# power_section.net
KiCad netlist of a schematic drawn in Altium Designer
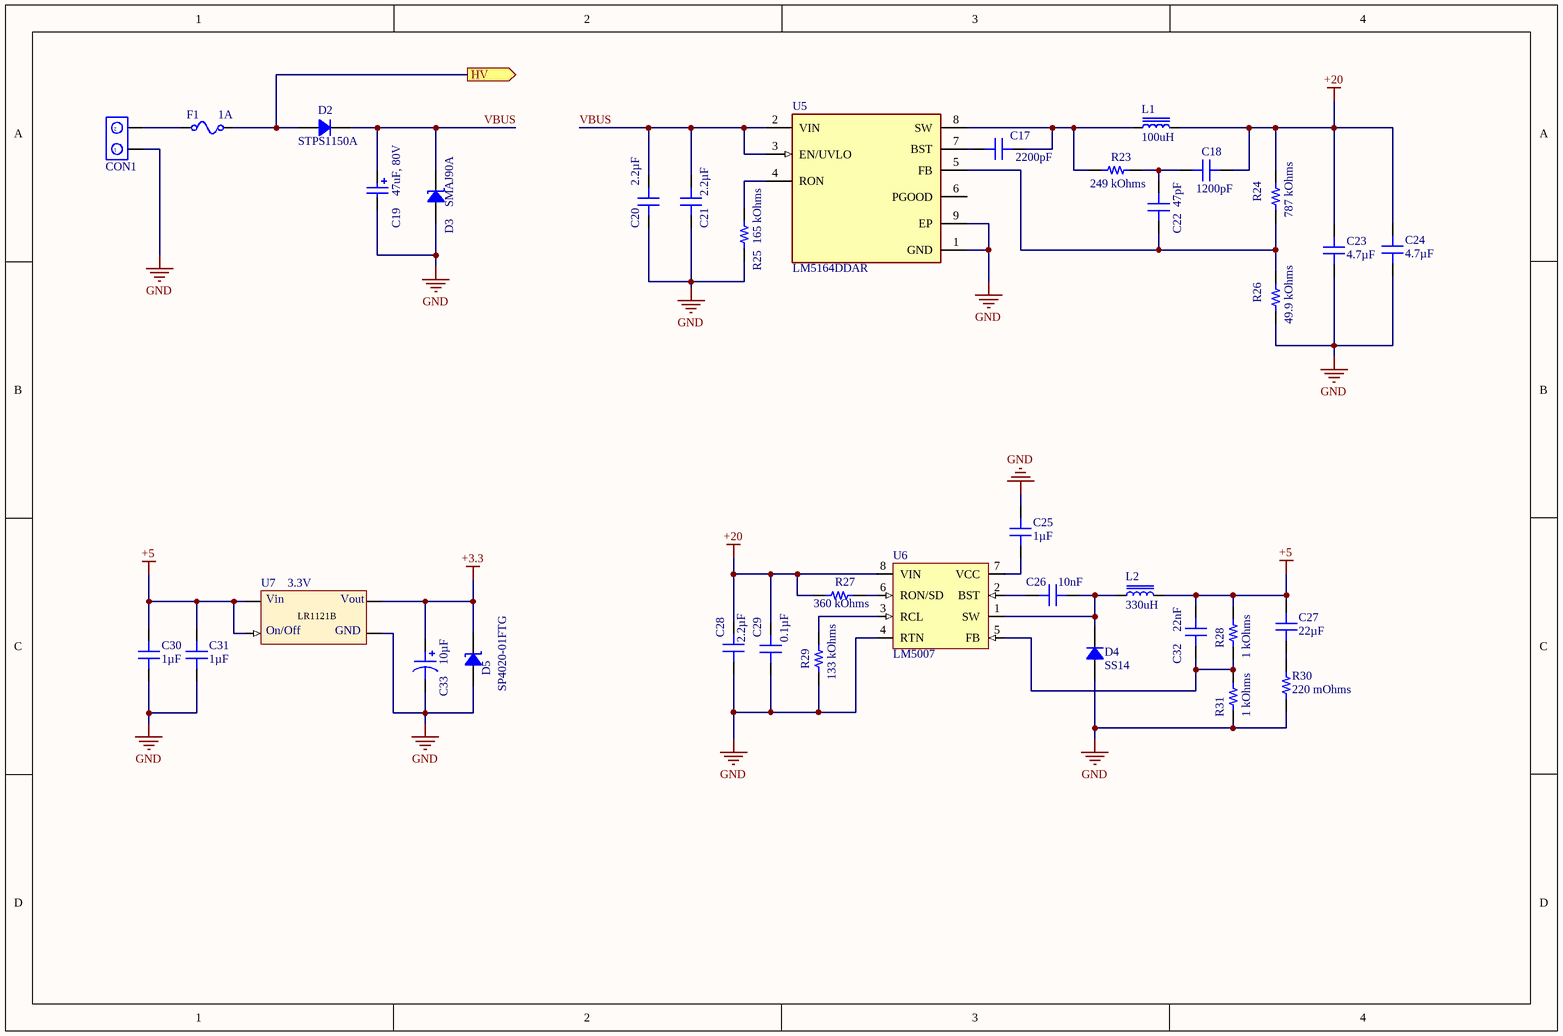
[diagram p0: power section.SchDoc]

(export (version "E")
  (design (tool "Eeschema 10.0.6"))
  (components
    (comp (ref "C17")
      (value "2200pF")
      (footprint "CAP 1206_3216 - 1.2MM")
      (description "CAP CER 1206 2.2NF 100V C0G")
      (fields (field (name "PART NUMBER") "C1206C222K1GECAUTO") (field (name "MANUFACTURER") "KEMET"))
      (libsource (lib "Celestial Altium Library - altium_library") (part "Capacitor"))
    )
    (comp (ref "C18")
      (value "1200pF")
      (footprint "CAP 0603_1608")
      (description "CAP CER 1200PF 100V X7R 0603")
      (fields (field (name "PART NUMBER") "C0603C122K1RAC7867") (field (name "MANUFACTURER") "KEMET"))
      (libsource (lib "Celestial Altium Library - altium_library") (part "Capacitor"))
    )
    (comp (ref "C19")
      (value "47uF, 80V")
      (footprint "WCAP-ASLI_D10H10.5")
      (description "WCAP-ASLI Aluminum Electrolytic Capacitor, V-Chip, SMT, D10xH10.5mm, 47uF, 80V")
      (fields
        (field (name "MANUFACTURER PART NUMBER") "865081757008")
        (field (name "MANUFACTURER") "Wurth Elektronik")
      )
      (libsource (lib "Altium_WCAP-ASLI_rev20b") (part "865081757008"))
    )
    (comp (ref "C20")
      (value "2.2µF")
      (footprint "CAP 1210_3225 - 2.8MM")
      (description "CAP CER 2.2UF 100V X7R 1210")
      (fields (field (name "PART NUMBER") "HMK325B7225KM-P") (field (name "MANUFACTURER") "Taiyo Yuden"))
      (libsource (lib "Celestial Altium Library - altium_library") (part "Capacitor"))
    )
    (comp (ref "C21")
      (value "2.2µF")
      (footprint "CAP 1210_3225 - 2.8MM")
      (description "CAP CER 2.2UF 100V X7R 1210")
      (fields (field (name "PART NUMBER") "HMK325B7225KM-P") (field (name "MANUFACTURER") "Taiyo Yuden"))
      (libsource (lib "Celestial Altium Library - altium_library") (part "Capacitor"))
    )
    (comp (ref "C22")
      (value "47pF")
      (footprint "CAP 0603_1608")
      (description "CAP CER 47PF 100V C0G/NP0 0603")
      (fields (field (name "PART NUMBER") "06031A470FAT2A") (field (name "MANUFACTURER") "AVX Corporation"))
      (libsource (lib "Celestial Altium Library - altium_library") (part "Capacitor"))
    )
    (comp (ref "C23")
      (value "4.7µF")
      (footprint "CAP 0805_2012")
      (description "CAP CER 4.7UF 50V X5R 0805")
      (fields
        (field (name "PART NUMBER") "CL21A475KBQNNNE")
        (field (name "MANUFACTURER") "Samsung Electro-Mechanics")
      )
      (libsource (lib "Celestial Altium Library - altium_library") (part "Capacitor"))
    )
    (comp (ref "C24")
      (value "4.7µF")
      (footprint "CAP 0805_2012")
      (description "CAP CER 4.7UF 50V X5R 0805")
      (fields
        (field (name "PART NUMBER") "CL21A475KBQNNNE")
        (field (name "MANUFACTURER") "Samsung Electro-Mechanics")
      )
      (libsource (lib "Celestial Altium Library - altium_library") (part "Capacitor"))
    )
    (comp (ref "C25")
      (value "1µF")
      (footprint "CAP 0805_2012")
      (description "CAP CER 1UF 50V X7R 0805")
      (fields
        (field (name "PART NUMBER") "GCM21BR71H105KA03L")
        (field (name "MANUFACTURER") "Murata Electronics")
      )
      (libsource (lib "Celestial Altium Library - altium_library") (part "Capacitor"))
    )
    (comp (ref "C26")
      (value "10nF")
      (footprint "CAP 0402_1005")
      (description "CAP CER 0402 10NF 16V X7R 10%")
      (fields (field (name "PART NUMBER") "C0402C103K4RECAUTO") (field (name "MANUFACTURER") "KEMET"))
      (libsource (lib "Celestial Altium Library - altium_library") (part "Capacitor"))
    )
    (comp (ref "C27")
      (value "22µF")
      (footprint "CAP 1210_3225 - 2.8MM")
      (description "CAP CER 22UF 25V X7R 1210")
      (fields
        (field (name "PART NUMBER") "C3225X7R1E226M250AB")
        (field (name "MANUFACTURER") "TDK Corporation")
      )
      (libsource (lib "Celestial Altium Library - altium_library") (part "Capacitor"))
    )
    (comp (ref "C28")
      (value "2.2µF")
      (footprint "CAP 1206_3216 - 1.0MM")
      (description "CAP CER 2.2UF 50V X7R 1206")
      (fields (field (name "PART NUMBER") "UMK316B7225MD-T") (field (name "MANUFACTURER") "Taiyo Yuden"))
      (libsource (lib "Celestial Altium Library - altium_library") (part "Capacitor"))
    )
    (comp (ref "C29")
      (value "0.1µF")
      (footprint "CAP 0805_2012")
      (description "CAP CER 0805 10% X8R 50V 100NF")
      (fields (field (name "PART NUMBER") "AC0805KKX8R9BB104") (field (name "MANUFACTURER") "Yageo"))
      (libsource (lib "Celestial Altium Library - altium_library") (part "Capacitor"))
    )
    (comp (ref "C30")
      (value "1µF")
      (footprint "CAP 0402_1005")
      (description "CAP CER 1UF 10V X7S 0402")
      (fields
        (field (name "PART NUMBER") "GRM155C71A105KE11D")
        (field (name "MANUFACTURER") "Murata Electronics")
      )
      (libsource (lib "Celestial Altium Library - altium_library") (part "Capacitor"))
    )
    (comp (ref "C31")
      (value "1µF")
      (footprint "CAP 0402_1005")
      (description "CAP CER 1UF 10V X7S 0402")
      (fields
        (field (name "PART NUMBER") "GRM155C71A105KE11D")
        (field (name "MANUFACTURER") "Murata Electronics")
      )
      (libsource (lib "Celestial Altium Library - altium_library") (part "Capacitor"))
    )
    (comp (ref "C32")
      (value "22nF")
      (footprint "CAP 0603_1608")
      (description "CAP CER 2200PF 50V X7R 0603")
      (fields (field (name "PART NUMBER") "06035C222JAT2A") (field (name "MANUFACTURER") "AVX Corporation"))
      (libsource (lib "Celestial Altium Library - altium_library") (part "Capacitor"))
    )
    (comp (ref "C33")
      (value "10µF")
      (footprint "CAP POL 1206_3216")
      (description "CAP TANT 10UF 10% 10V 1206")
      (fields (field (name "PART NUMBER") "T491S106K010AT") (field (name "MANUFACTURER") "KEMET"))
      (libsource (lib "Celestial Altium Library - altium_library") (part "Polarised Capacitor"))
    )
    (comp (ref "CON1")
      (value "DG301-5.0-02P-12-00AH")
      (footprint "DG301-5.0-02P-12-00AH")
      (libsource (lib "My_Library_PCB_Terminal") (part "DG301-5.0-02P-12-00AH"))
    )
    (comp (ref "D2")
      (value "STPS1150A")
      (footprint "DO214AC SMA")
      (description "DIODE SCHOTTKY 150V 1A SMA")
      (fields (field (name "MANUFACTURER") "STMicroelectronics"))
      (libsource (lib "Celestial Altium Library - altium_library") (part "Diode"))
    )
    (comp (ref "D3")
      (value "SMAJ90A")
      (footprint "DO214AC SMA")
      (description "TVS DIODE 90V 146V SMA")
      (fields (field (name "MANUFACTURER") "AVX Corporation"))
      (libsource (lib "Celestial Altium Library - altium_library") (part "DIODE TVS UNI"))
    )
    (comp (ref "D4")
      (value "SS14")
      (footprint "DO214AC SMA")
      (description "DIODE SCHOTTKY 40V 1A SMA")
      (fields (field (name "MANUFACTURER") "ON Semiconductor"))
      (libsource (lib "Celestial Altium Library - altium_library") (part "Diode"))
    )
    (comp (ref "D5")
      (value "SP4020-01FTG")
      (footprint "SOD323")
      (description "TVS DIODE 3.3V 21.8V SOD323")
      (fields (field (name "MANUFACTURER") "Littelfuse Inc."))
      (libsource (lib "Celestial Altium Library - altium_library") (part "DIODE TVS UNI"))
    )
    (comp (ref "F1")
      (value "1A")
      (footprint "5x20 fuse holder clip R3-5A")
      (description "5x20 fuse holder clip")
      (libsource (lib "My_Library_Fuse") (part "5x20 fuse"))
    )
    (comp (ref "L1")
      (value "100uH")
      (footprint "WE-PD_1245")
      (description "330uh 1A Shielded Fixed inductor COREMASTER")
      (fields (field (name "TOLERANCE") "20%"))
      (libsource (lib "My_Library_Fixed_Inductor") (part "CDRH127-101M"))
    )
    (comp (ref "L2")
      (value "330uH")
      (footprint "WE-PD_1245")
      (description "330uh 1A Shielded Fixed inductor COREMASTER")
      (fields (field (name "TOLERANCE") "20%"))
      (libsource (lib "My_Library_Fixed_Inductor") (part "SRI1204-331M"))
    )
    (comp (ref "R23")
      (value "249 kOhms")
      (footprint "RES 1206_3216")
      (description "RES SMD 249K OHM 1% 1/4W 1206")
      (fields (field (name "PART NUMBER") "CRCW1206249KFKEA") (field (name "MANUFACTURER") "Vishay Dale"))
      (libsource (lib "Celestial Altium Library - altium_library") (part "Resistor"))
    )
    (comp (ref "R24")
      (value "787 kOhms")
      (footprint "RES 1206_3216")
      (description "RES 787K OHM 1% 1/4W 1206")
      (fields
        (field (name "PART NUMBER") "RMCF1206FT787K")
        (field (name "MANUFACTURER") "Stackpole Electronics Inc")
      )
      (libsource (lib "Celestial Altium Library - altium_library") (part "Resistor"))
    )
    (comp (ref "R25")
      (value "165 kOhms")
      (footprint "RES 1206_3216")
      (description "RES SMD 165K OHM 1% 1/4W 1206")
      (fields (field (name "PART NUMBER") "CRCW1206165KFKEA") (field (name "MANUFACTURER") "Vishay Dale"))
      (libsource (lib "Celestial Altium Library - altium_library") (part "Resistor"))
    )
    (comp (ref "R26")
      (value "49.9 kOhms")
      (footprint "RES 1206_3216")
      (description "RES SMD 49.9K OHM 1% 1/4W 1206")
      (fields (field (name "PART NUMBER") "AC1206FR-0749K9L") (field (name "MANUFACTURER") "Yageo"))
      (libsource (lib "Celestial Altium Library - altium_library") (part "Resistor"))
    )
    (comp (ref "R27")
      (value "360 kOhms")
      (footprint "RES 1206_3216")
      (description "RES SMD 360K OHM 1% 1/4W 1206")
      (fields (field (name "PART NUMBER") "RC1206FR-07360KL") (field (name "MANUFACTURER") "Yageo"))
      (libsource (lib "Celestial Altium Library - altium_library") (part "Resistor"))
    )
    (comp (ref "R28")
      (value "1 kOhms")
      (footprint "RES 1206_3216")
      (description "RES SMD 1K OHM 1% 1/4W 1206")
      (fields (field (name "PART NUMBER") "RC1206FR-071KL") (field (name "MANUFACTURER") "Yageo"))
      (libsource (lib "Celestial Altium Library - altium_library") (part "Resistor"))
    )
    (comp (ref "R29")
      (value "133 kOhms")
      (footprint "RES 1206_3216")
      (description "RES SMD 133K OHM 1% 1/4W 1206")
      (fields (field (name "PART NUMBER") "RC1206FR-07133KL") (field (name "MANUFACTURER") "Yageo"))
      (libsource (lib "Celestial Altium Library - altium_library") (part "Resistor"))
    )
    (comp (ref "R30")
      (value "220 mOhms")
      (footprint "RES 1206_3216")
      (description "RES 0.22 OHM 1% 1/4W 1206")
      (fields
        (field (name "PART NUMBER") "RMCF1206FTR220")
        (field (name "MANUFACTURER") "Stackpole Electronics Inc")
      )
      (libsource (lib "Celestial Altium Library - altium_library") (part "Resistor"))
    )
    (comp (ref "R31")
      (value "1 kOhms")
      (footprint "RES 1206_3216")
      (description "RES SMD 1K OHM 1% 1/4W 1206")
      (fields (field (name "PART NUMBER") "RC1206FR-071KL") (field (name "MANUFACTURER") "Yageo"))
      (libsource (lib "Celestial Altium Library - altium_library") (part "Resistor"))
    )
    (comp (ref "U5")
      (value "LM5164DDAR")
      (footprint "FP-DDA0008E-IPC_A")
      (description "POWER MANAGEMENT")
      (fields
        (field (name "MANUFACTURER") "Texas Instruments")
        (field (name "OCTOPART") "https://octopart.com/lm5164ddar-texas+instruments-96785744")
      )
      (libsource (lib "My_Library_DCDC_Switching_Regulators") (part "LM5164DDAR"))
    )
    (comp (ref "U6")
      (value "LM5007")
      (footprint "DGK0008A_L")
      (description "High Voltage (80V) Step Down Switching Regulator, 8-pin MSOP")
      (fields (field (name "MANUFACTURER") "Texas Instruments"))
      (libsource (lib "My_Library_Switching_Regulators") (part "LM5007MM"))
    )
    (comp (ref "U7")
      (value "3.3V")
      (footprint "SOT25_LR2111")
      (description "200mA 7V LDO")
      (libsource (lib "My_Library_Linear_Regulator") (part "LR1121B_3V3"))
    )
  )
  (nets
    (net (code "1") (name "+3.3") (class "Default")
      (node (ref "C33") (pin "1") (pinfunction "1_1") (pintype "passive"))
      (node (ref "D5") (pin "2") (pinfunction "2_2") (pintype "passive"))
      (node (ref "U7") (pin "1") (pinfunction "Vout_1") (pintype "power_in"))
    )
    (net (code "2") (name "+5") (class "Default")
      (node (ref "C27") (pin "2") (pinfunction "2_2") (pintype "passive"))
      (node (ref "C30") (pin "2") (pinfunction "2_2") (pintype "passive"))
      (node (ref "C31") (pin "2") (pinfunction "2_2") (pintype "passive"))
      (node (ref "C32") (pin "2") (pinfunction "2_2") (pintype "passive"))
      (node (ref "L2") (pin "2") (pinfunction "2_2") (pintype "passive"))
      (node (ref "R28") (pin "2") (pinfunction "2_2") (pintype "passive"))
      (node (ref "U7") (pin "3") (pinfunction "Vin_3") (pintype "power_in"))
      (node (ref "U7") (pin "4") (pinfunction "ON/OFF_4") (pintype "input"))
    )
    (net (code "3") (name "+20") (class "Default")
      (node (ref "C18") (pin "1") (pinfunction "1_1") (pintype "passive"))
      (node (ref "C23") (pin "2") (pinfunction "2_2") (pintype "passive"))
      (node (ref "C24") (pin "2") (pinfunction "2_2") (pintype "passive"))
      (node (ref "C28") (pin "2") (pinfunction "2_2") (pintype "passive"))
      (node (ref "C29") (pin "2") (pinfunction "2_2") (pintype "passive"))
      (node (ref "L1") (pin "2") (pinfunction "2_2") (pintype "passive"))
      (node (ref "R24") (pin "2") (pinfunction "2_2") (pintype "passive"))
      (node (ref "R27") (pin "1") (pinfunction "1_1") (pintype "passive"))
      (node (ref "U6") (pin "8") (pinfunction "VIN_8") (pintype "power_in"))
    )
    (net (code "4") (name "/HV") (class "Default")
      (node (ref "D2") (pin "1") (pinfunction "1_1") (pintype "passive"))
      (node (ref "F1") (pin "2") (pinfunction "2_2") (pintype "passive"))
    )
    (net (code "5") (name "/VBUS") (class "Default")
      (node (ref "C19") (pin "1") (pinfunction "P_1") (pintype "passive"))
      (node (ref "C20") (pin "2") (pinfunction "2_2") (pintype "passive"))
      (node (ref "C21") (pin "2") (pinfunction "2_2") (pintype "passive"))
      (node (ref "D2") (pin "2") (pinfunction "2_2") (pintype "passive"))
      (node (ref "D3") (pin "2") (pinfunction "2_2") (pintype "passive"))
      (node (ref "U5") (pin "2") (pinfunction "VIN_2") (pintype "power_in"))
      (node (ref "U5") (pin "3") (pinfunction "EN/UVLO_3") (pintype "input"))
    )
    (net (code "6") (name "GND") (class "Default")
      (node (ref "C19") (pin "2") (pinfunction "N_2") (pintype "passive"))
      (node (ref "C20") (pin "1") (pinfunction "1_1") (pintype "passive"))
      (node (ref "C21") (pin "1") (pinfunction "1_1") (pintype "passive"))
      (node (ref "C23") (pin "1") (pinfunction "1_1") (pintype "passive"))
      (node (ref "C24") (pin "1") (pinfunction "1_1") (pintype "passive"))
      (node (ref "C25") (pin "1") (pinfunction "1_1") (pintype "passive"))
      (node (ref "C28") (pin "1") (pinfunction "1_1") (pintype "passive"))
      (node (ref "C29") (pin "1") (pinfunction "1_1") (pintype "passive"))
      (node (ref "C30") (pin "1") (pinfunction "1_1") (pintype "passive"))
      (node (ref "C31") (pin "1") (pinfunction "1_1") (pintype "passive"))
      (node (ref "C33") (pin "2") (pinfunction "2_2") (pintype "passive"))
      (node (ref "CON1") (pin "1") (pinfunction "1_1") (pintype "passive"))
      (node (ref "D3") (pin "1") (pinfunction "1_1") (pintype "passive"))
      (node (ref "D4") (pin "1") (pinfunction "1_1") (pintype "passive"))
      (node (ref "D5") (pin "1") (pinfunction "1_1") (pintype "passive"))
      (node (ref "R25") (pin "1") (pinfunction "1_1") (pintype "passive"))
      (node (ref "R26") (pin "1") (pinfunction "1_1") (pintype "passive"))
      (node (ref "R29") (pin "1") (pinfunction "1_1") (pintype "passive"))
      (node (ref "R30") (pin "1") (pinfunction "1_1") (pintype "passive"))
      (node (ref "R31") (pin "1") (pinfunction "1_1") (pintype "passive"))
      (node (ref "U5") (pin "1") (pinfunction "GND_1") (pintype "power_in"))
      (node (ref "U5") (pin "9") (pinfunction "EP_9") (pintype "passive"))
      (node (ref "U6") (pin "4") (pinfunction "RTN_4") (pintype "power_in"))
      (node (ref "U7") (pin "2") (pinfunction "Vss_2") (pintype "passive"))
    )
    (net (code "7") (name "Net-(C18-Pad2)") (class "Default")
      (node (ref "C18") (pin "2") (pinfunction "2_2") (pintype "passive"))
      (node (ref "C22") (pin "2") (pinfunction "2_2") (pintype "passive"))
      (node (ref "R23") (pin "1") (pinfunction "1_1") (pintype "passive"))
    )
    (net (code "8") (name "Net-(C27-Pad1)") (class "Default")
      (node (ref "C27") (pin "1") (pinfunction "1_1") (pintype "passive"))
      (node (ref "R30") (pin "2") (pinfunction "2_2") (pintype "passive"))
    )
    (net (code "9") (name "Net-(CON1-Pad2)") (class "Default")
      (node (ref "CON1") (pin "2") (pinfunction "2_2") (pintype "passive"))
      (node (ref "F1") (pin "1") (pinfunction "1_1") (pintype "passive"))
    )
    (net (code "10") (name "Net-(U5-BST)") (class "Default")
      (node (ref "C17") (pin "2") (pinfunction "2_2") (pintype "passive"))
      (node (ref "U5") (pin "7") (pinfunction "BST_7") (pintype "passive"))
    )
    (net (code "11") (name "Net-(U5-FB)") (class "Default")
      (node (ref "C22") (pin "1") (pinfunction "1_1") (pintype "passive"))
      (node (ref "R24") (pin "1") (pinfunction "1_1") (pintype "passive"))
      (node (ref "R26") (pin "2") (pinfunction "2_2") (pintype "passive"))
      (node (ref "U5") (pin "5") (pinfunction "FB_5") (pintype "passive"))
    )
    (net (code "12") (name "Net-(U5-RON)") (class "Default")
      (node (ref "R25") (pin "2") (pinfunction "2_2") (pintype "passive"))
      (node (ref "U5") (pin "4") (pinfunction "RON_4") (pintype "passive"))
    )
    (net (code "13") (name "Net-(U5-SW)") (class "Default")
      (node (ref "C17") (pin "1") (pinfunction "1_1") (pintype "passive"))
      (node (ref "L1") (pin "1") (pinfunction "1_1") (pintype "passive"))
      (node (ref "R23") (pin "2") (pinfunction "2_2") (pintype "passive"))
      (node (ref "U5") (pin "8") (pinfunction "SW_8") (pintype "passive"))
    )
    (net (code "14") (name "Net-(U6-BST)") (class "Default")
      (node (ref "C26") (pin "1") (pinfunction "1_1") (pintype "passive"))
      (node (ref "U6") (pin "2") (pinfunction "BST_2") (pintype "input"))
    )
    (net (code "15") (name "Net-(U6-FB)") (class "Default")
      (node (ref "C32") (pin "1") (pinfunction "1_1") (pintype "passive"))
      (node (ref "R28") (pin "1") (pinfunction "1_1") (pintype "passive"))
      (node (ref "R31") (pin "2") (pinfunction "2_2") (pintype "passive"))
      (node (ref "U6") (pin "5") (pinfunction "FB_5") (pintype "input"))
    )
    (net (code "16") (name "Net-(U6-RCL)") (class "Default")
      (node (ref "R29") (pin "2") (pinfunction "2_2") (pintype "passive"))
      (node (ref "U6") (pin "3") (pinfunction "RCL_3") (pintype "input"))
    )
    (net (code "17") (name "Net-(U6-RON{slash}SD)") (class "Default")
      (node (ref "R27") (pin "2") (pinfunction "2_2") (pintype "passive"))
      (node (ref "U6") (pin "6") (pinfunction "RON/SD_6") (pintype "input"))
    )
    (net (code "18") (name "Net-(U6-SW)") (class "Default")
      (node (ref "C26") (pin "2") (pinfunction "2_2") (pintype "passive"))
      (node (ref "D4") (pin "2") (pinfunction "2_2") (pintype "passive"))
      (node (ref "L2") (pin "1") (pinfunction "1_1") (pintype "passive"))
      (node (ref "U6") (pin "1") (pinfunction "SW_1") (pintype "power_in"))
    )
    (net (code "19") (name "Net-(U6-VCC)") (class "Default")
      (node (ref "C25") (pin "2") (pinfunction "2_2") (pintype "passive"))
      (node (ref "U6") (pin "7") (pinfunction "VCC_7") (pintype "power_in"))
    )
    (net (code "20") (name "unconnected-(U5-PGOOD-Pad6)") (class "Default")
      (node (ref "U5") (pin "6") (pinfunction "PGOOD_6") (pintype "open_collector"))
    )
  )
)
